# Sheet1.net
KiCad netlist of a schematic drawn in Altium Designer
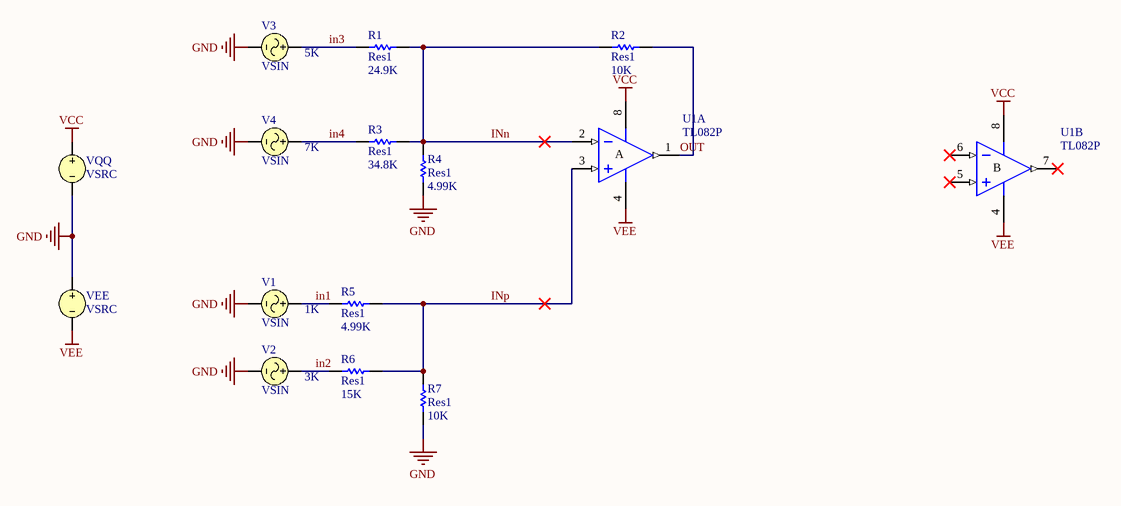
[diagram p0: Sheet1.SchDoc]

(export (version "E")
  (design (tool "Eeschema 10.0.6"))
  (components
    (comp (ref "R1")
      (value "Res1")
      (footprint "AXIAL-0.3")
      (description "Resistor")
      (fields (field (name "ALTIUM_VALUE") "24.9K") (field (name "PUBLISHER") "Altium Limited"))
      (libsource (lib "Miscellaneous Devices") (part "Res1"))
    )
    (comp (ref "R2")
      (value "Res1")
      (footprint "AXIAL-0.3")
      (description "Resistor")
      (fields (field (name "ALTIUM_VALUE") "10K") (field (name "PUBLISHER") "Altium Limited"))
      (libsource (lib "Miscellaneous Devices") (part "Res1"))
    )
    (comp (ref "R3")
      (value "Res1")
      (footprint "AXIAL-0.3")
      (description "Resistor")
      (fields (field (name "ALTIUM_VALUE") "34.8K") (field (name "PUBLISHER") "Altium Limited"))
      (libsource (lib "Miscellaneous Devices") (part "Res1"))
    )
    (comp (ref "R4")
      (value "Res1")
      (footprint "AXIAL-0.3")
      (description "Resistor")
      (fields (field (name "ALTIUM_VALUE") "4.99K") (field (name "PUBLISHER") "Altium Limited"))
      (libsource (lib "Miscellaneous Devices") (part "Res1"))
    )
    (comp (ref "R5")
      (value "Res1")
      (footprint "AXIAL-0.3")
      (description "Resistor")
      (fields (field (name "ALTIUM_VALUE") "4.99K") (field (name "PUBLISHER") "Altium Limited"))
      (libsource (lib "Miscellaneous Devices") (part "Res1"))
    )
    (comp (ref "R6")
      (value "Res1")
      (footprint "AXIAL-0.3")
      (description "Resistor")
      (fields (field (name "ALTIUM_VALUE") "15K") (field (name "PUBLISHER") "Altium Limited"))
      (libsource (lib "Miscellaneous Devices") (part "Res1"))
    )
    (comp (ref "R7")
      (value "Res1")
      (footprint "AXIAL-0.3")
      (description "Resistor")
      (fields (field (name "ALTIUM_VALUE") "10K") (field (name "PUBLISHER") "Altium Limited"))
      (libsource (lib "Miscellaneous Devices") (part "Res1"))
    )
    (comp (ref "U1")
      (value "TL082P")
      (footprint "P008")
      (description "JFET-Input Operational Amplifier")
      (fields (field (name "PUBLISHER") "Altium Limited"))
      (libsource (lib "TI Operational Amplifier") (part "TL082P"))
    )
    (comp (ref "V1")
      (value "VSIN")
      (description "Sinusoidal Voltage Source")
      (fields (field (name "FREQUENCY") "1K") (field (name "PUBLISHER") "Altium Limited"))
      (libsource (lib "Simulation Sources") (part "VSIN"))
    )
    (comp (ref "V2")
      (value "VSIN")
      (description "Sinusoidal Voltage Source")
      (fields (field (name "FREQUENCY") "3K") (field (name "PUBLISHER") "Altium Limited"))
      (libsource (lib "Simulation Sources") (part "VSIN"))
    )
    (comp (ref "V3")
      (value "VSIN")
      (description "Sinusoidal Voltage Source")
      (fields (field (name "FREQUENCY") "5K") (field (name "PUBLISHER") "Altium Limited"))
      (libsource (lib "Simulation Sources") (part "VSIN"))
    )
    (comp (ref "V4")
      (value "VSIN")
      (description "Sinusoidal Voltage Source")
      (fields (field (name "FREQUENCY") "7K") (field (name "PUBLISHER") "Altium Limited"))
      (libsource (lib "Simulation Sources") (part "VSIN"))
    )
    (comp (ref "VEE")
      (value "VSRC")
      (description "Voltage Source")
      (fields (field (name "PUBLISHER") "Altium Limited"))
      (libsource (lib "Simulation Sources") (part "VSRC"))
    )
    (comp (ref "VQQ")
      (value "VSRC")
      (description "Voltage Source")
      (fields (field (name "PUBLISHER") "Altium Limited"))
      (libsource (lib "Simulation Sources") (part "VSRC"))
    )
  )
  (nets
    (net (code "1") (name "/INn") (class "Default")
      (node (ref "R1") (pin "2") (pinfunction "2_2") (pintype "passive"))
      (node (ref "R2") (pin "1") (pinfunction "1_1") (pintype "passive"))
      (node (ref "R3") (pin "2") (pinfunction "2_2") (pintype "passive"))
      (node (ref "R4") (pin "2") (pinfunction "2_2") (pintype "passive"))
      (node (ref "U1") (pin "2") (pinfunction "IN-_2") (pintype "input"))
    )
    (net (code "2") (name "/INp") (class "Default")
      (node (ref "R5") (pin "2") (pinfunction "2_2") (pintype "passive"))
      (node (ref "R6") (pin "2") (pinfunction "2_2") (pintype "passive"))
      (node (ref "R7") (pin "2") (pinfunction "2_2") (pintype "passive"))
      (node (ref "U1") (pin "3") (pinfunction "IN+_3") (pintype "input"))
    )
    (net (code "3") (name "/OUT") (class "Default")
      (node (ref "R2") (pin "2") (pinfunction "2_2") (pintype "passive"))
      (node (ref "U1") (pin "1") (pinfunction "OUT_1") (pintype "output"))
    )
    (net (code "4") (name "/in1") (class "Default")
      (node (ref "R5") (pin "1") (pinfunction "1_1") (pintype "passive"))
      (node (ref "V1") (pin "1") (pinfunction "1_1") (pintype "passive"))
    )
    (net (code "5") (name "/in2") (class "Default")
      (node (ref "R6") (pin "1") (pinfunction "1_1") (pintype "passive"))
      (node (ref "V2") (pin "1") (pinfunction "1_1") (pintype "passive"))
    )
    (net (code "6") (name "/in3") (class "Default")
      (node (ref "R1") (pin "1") (pinfunction "1_1") (pintype "passive"))
      (node (ref "V3") (pin "1") (pinfunction "1_1") (pintype "passive"))
    )
    (net (code "7") (name "/in4") (class "Default")
      (node (ref "R3") (pin "1") (pinfunction "1_1") (pintype "passive"))
      (node (ref "V4") (pin "1") (pinfunction "1_1") (pintype "passive"))
    )
    (net (code "8") (name "GND") (class "Default")
      (node (ref "R4") (pin "1") (pinfunction "1_1") (pintype "passive"))
      (node (ref "R7") (pin "1") (pinfunction "1_1") (pintype "passive"))
      (node (ref "V1") (pin "2") (pinfunction "2_2") (pintype "passive"))
      (node (ref "V2") (pin "2") (pinfunction "2_2") (pintype "passive"))
      (node (ref "V3") (pin "2") (pinfunction "2_2") (pintype "passive"))
      (node (ref "V4") (pin "2") (pinfunction "2_2") (pintype "passive"))
      (node (ref "VEE") (pin "1") (pinfunction "1_1") (pintype "passive"))
      (node (ref "VQQ") (pin "2") (pinfunction "2_2") (pintype "passive"))
    )
    (net (code "9") (name "VCC") (class "Default")
      (node (ref "U1") (pin "8") (pinfunction "V+_8") (pintype "power_in"))
      (node (ref "VQQ") (pin "1") (pinfunction "1_1") (pintype "passive"))
    )
    (net (code "10") (name "VEE") (class "Default")
      (node (ref "U1") (pin "4") (pinfunction "V-_4") (pintype "power_in"))
      (node (ref "VEE") (pin "2") (pinfunction "2_2") (pintype "passive"))
    )
    (net (code "11") (name "unconnected-(U1B-IN+-Pad5)") (class "Default")
      (node (ref "U1") (pin "5") (pinfunction "IN+_5") (pintype "input+no_connect"))
    )
    (net (code "12") (name "unconnected-(U1B-IN--Pad6)") (class "Default")
      (node (ref "U1") (pin "6") (pinfunction "IN-_6") (pintype "input+no_connect"))
    )
    (net (code "13") (name "unconnected-(U1B-OUT-Pad7)") (class "Default")
      (node (ref "U1") (pin "7") (pinfunction "OUT_7") (pintype "output+no_connect"))
    )
  )
)
